# Sheet_this.net
KiCad netlist of a schematic drawn in Altium Designer
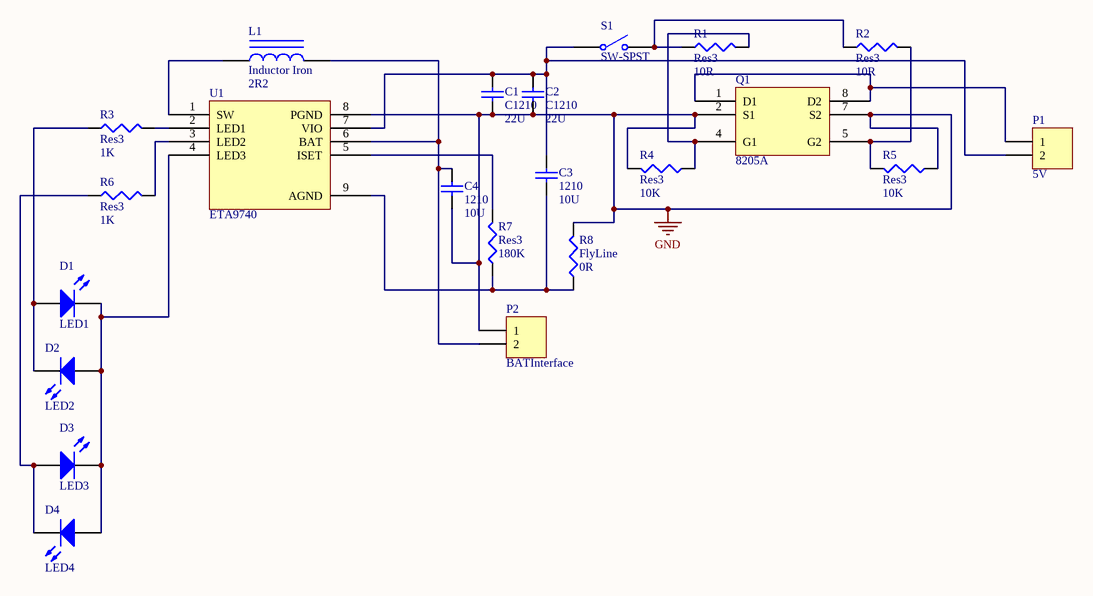
[diagram p0: Sheet.this.SchDoc]

(export (version "E")
  (design (tool "Eeschema 10.0.6"))
  (components
    (comp (ref "C1")
      (value "C1210")
      (footprint "C1210")
      (description "Capacitor")
      (fields (field (name "ALTIUM_VALUE") "22U") (field (name "PUBLISHER") "Altium Limited"))
      (libsource (lib "Miscellaneous Devices") (part "Cap"))
    )
    (comp (ref "C2")
      (value "C1210")
      (footprint "C1210")
      (description "Capacitor")
      (fields (field (name "ALTIUM_VALUE") "22U") (field (name "PUBLISHER") "Altium Limited"))
      (libsource (lib "Miscellaneous Devices") (part "Cap"))
    )
    (comp (ref "C3")
      (value "1210")
      (description "Capacitor")
      (fields (field (name "ALTIUM_VALUE") "10U") (field (name "PUBLISHER") "Altium Limited"))
      (libsource (lib "Miscellaneous Devices") (part "Cap"))
    )
    (comp (ref "C4")
      (value "1210")
      (description "Capacitor")
      (fields (field (name "ALTIUM_VALUE") "10U") (field (name "PUBLISHER") "Altium Limited"))
      (libsource (lib "Miscellaneous Devices") (part "Cap"))
    )
    (comp (ref "D1")
      (value "LED1")
      (footprint "0805D")
      (description "Typical RED, GREEN, YELLOW, AMBER GaAs LED")
      (fields (field (name "PUBLISHER") "Altium Limited"))
      (libsource (lib "Miscellaneous Devices") (part "LED2"))
    )
    (comp (ref "D2")
      (value "LED2")
      (footprint "0805D")
      (description "Typical RED, GREEN, YELLOW, AMBER GaAs LED")
      (fields (field (name "PUBLISHER") "Altium Limited"))
      (libsource (lib "Miscellaneous Devices") (part "LED2"))
    )
    (comp (ref "D3")
      (value "LED3")
      (footprint "0805D")
      (description "Typical RED, GREEN, YELLOW, AMBER GaAs LED")
      (fields (field (name "PUBLISHER") "Altium Limited"))
      (libsource (lib "Miscellaneous Devices") (part "LED2"))
    )
    (comp (ref "D4")
      (value "LED4")
      (footprint "0805D")
      (description "Typical RED, GREEN, YELLOW, AMBER GaAs LED")
      (fields (field (name "PUBLISHER") "Altium Limited"))
      (libsource (lib "Miscellaneous Devices") (part "LED2"))
    )
    (comp (ref "L1")
      (value "Inductor Iron")
      (footprint "L_7x7")
      (description "Magnetic-Core Inductor")
      (fields (field (name "ALTIUM_VALUE") "2R2") (field (name "PUBLISHER") "Altium Limited"))
      (libsource (lib "Miscellaneous Devices") (part "Inductor Iron"))
    )
    (comp (ref "P1")
      (value "5V")
      (footprint "HDR1X2")
      (description "Header, 2-Pin")
      (fields (field (name "PUBLISHER") "Altium Limited"))
      (libsource (lib "Miscellaneous Connectors") (part "Header 2"))
    )
    (comp (ref "P2")
      (value "BATInterface")
      (footprint "HDR1X2")
      (description "Header, 2-Pin, Right Angle")
      (fields (field (name "PUBLISHER") "Altium Limited"))
      (libsource (lib "Miscellaneous Connectors") (part "Header 2H"))
    )
    (comp (ref "Q1") (value "8205A") (footprint "TSSOP8") (libsource (lib "Schlib.this") (part "8205A")))
    (comp (ref "R1")
      (value "Res3")
      (footprint "0805")
      (description "Resistor")
      (fields (field (name "ALTIUM_VALUE") "10R") (field (name "PUBLISHER") "Altium Limited"))
      (libsource (lib "Miscellaneous Devices") (part "Res3"))
    )
    (comp (ref "R2")
      (value "Res3")
      (footprint "0805")
      (description "Resistor")
      (fields (field (name "ALTIUM_VALUE") "10R") (field (name "PUBLISHER") "Altium Limited"))
      (libsource (lib "Miscellaneous Devices") (part "Res3"))
    )
    (comp (ref "R3")
      (value "Res3")
      (footprint "0805")
      (description "Resistor")
      (fields (field (name "ALTIUM_VALUE") "1K") (field (name "PUBLISHER") "Altium Limited"))
      (libsource (lib "Miscellaneous Devices") (part "Res3"))
    )
    (comp (ref "R4")
      (value "Res3")
      (description "Resistor")
      (fields (field (name "ALTIUM_VALUE") "10K") (field (name "PUBLISHER") "Altium Limited"))
      (libsource (lib "Miscellaneous Devices") (part "Res3"))
    )
    (comp (ref "R5")
      (value "Res3")
      (description "Resistor")
      (fields (field (name "ALTIUM_VALUE") "10K") (field (name "PUBLISHER") "Altium Limited"))
      (libsource (lib "Miscellaneous Devices") (part "Res3"))
    )
    (comp (ref "R6")
      (value "Res3")
      (footprint "0805")
      (description "Resistor")
      (fields (field (name "ALTIUM_VALUE") "1K") (field (name "PUBLISHER") "Altium Limited"))
      (libsource (lib "Miscellaneous Devices") (part "Res3"))
    )
    (comp (ref "R7")
      (value "Res3")
      (footprint "0805")
      (description "Resistor")
      (fields (field (name "ALTIUM_VALUE") "180K") (field (name "PUBLISHER") "Altium Limited"))
      (libsource (lib "Miscellaneous Devices") (part "Res3"))
    )
    (comp (ref "R8")
      (value "FlyLine")
      (footprint "PFL1")
      (description "JP")
      (fields (field (name "ALTIUM_VALUE") "0R") (field (name "PUBLISHER") "Altium Limited"))
      (libsource (lib "Miscellaneous Devices") (part "Res3"))
    )
    (comp (ref "S1")
      (value "SW-SPST")
      (footprint "MSS22D18")
      (description "Single-Pole, Single-Throw Switch")
      (fields (field (name "PUBLISHER") "Altium Limited"))
      (libsource (lib "Miscellaneous Devices") (part "SW-SPST"))
    )
    (comp (ref "U1") (value "ETA9740") (footprint "SO-8H") (libsource (lib "Schlib.this") (part "ETA9740")))
  )
  (nets
    (net (code "1") (name "GND") (class "Default")
      (node (ref "C1") (pin "1") (pinfunction "1_1") (pintype "passive"))
      (node (ref "C2") (pin "1") (pinfunction "1_1") (pintype "passive"))
      (node (ref "C4") (pin "1") (pinfunction "1_1") (pintype "passive"))
      (node (ref "P2") (pin "1") (pinfunction "1_1") (pintype "passive"))
      (node (ref "Q1") (pin "2") (pinfunction "S1_2") (pintype "passive"))
      (node (ref "Q1") (pin "7") (pinfunction "S2_7") (pintype "passive"))
      (node (ref "R4") (pin "2") (pinfunction "2_2") (pintype "passive"))
      (node (ref "R5") (pin "1") (pinfunction "1_1") (pintype "passive"))
      (node (ref "R8") (pin "2") (pinfunction "2_2") (pintype "passive"))
      (node (ref "U1") (pin "8") (pinfunction "PGND_8") (pintype "passive"))
    )
    (net (code "2") (name "Net-(D1-A)") (class "Default")
      (node (ref "D1") (pin "1") (pinfunction "A_1") (pintype "passive"))
      (node (ref "D2") (pin "2") (pinfunction "K_2") (pintype "passive"))
      (node (ref "R3") (pin "1") (pinfunction "1_1") (pintype "passive"))
    )
    (net (code "3") (name "Net-(D1-K)") (class "Default")
      (node (ref "D1") (pin "2") (pinfunction "K_2") (pintype "passive"))
      (node (ref "D2") (pin "1") (pinfunction "A_1") (pintype "passive"))
      (node (ref "D3") (pin "2") (pinfunction "K_2") (pintype "passive"))
      (node (ref "D4") (pin "1") (pinfunction "A_1") (pintype "passive"))
      (node (ref "U1") (pin "4") (pinfunction "LED3_4") (pintype "passive"))
    )
    (net (code "4") (name "Net-(D3-A)") (class "Default")
      (node (ref "D3") (pin "1") (pinfunction "A_1") (pintype "passive"))
      (node (ref "D4") (pin "2") (pinfunction "K_2") (pintype "passive"))
      (node (ref "R6") (pin "1") (pinfunction "1_1") (pintype "passive"))
    )
    (net (code "5") (name "Net-(Q1-D1)") (class "Default")
      (node (ref "P1") (pin "1") (pinfunction "1_1") (pintype "passive"))
      (node (ref "Q1") (pin "1") (pinfunction "D1_1") (pintype "passive"))
      (node (ref "Q1") (pin "8") (pinfunction "D2_8") (pintype "passive"))
    )
    (net (code "6") (name "Net-(Q1-G1)") (class "Default")
      (node (ref "Q1") (pin "4") (pinfunction "G1_4") (pintype "passive"))
      (node (ref "R1") (pin "2") (pinfunction "2_2") (pintype "passive"))
      (node (ref "R4") (pin "1") (pinfunction "1_1") (pintype "passive"))
    )
    (net (code "7") (name "Net-(Q1-G2)") (class "Default")
      (node (ref "Q1") (pin "5") (pinfunction "G2_5") (pintype "passive"))
      (node (ref "R2") (pin "2") (pinfunction "2_2") (pintype "passive"))
      (node (ref "R5") (pin "2") (pinfunction "2_2") (pintype "passive"))
    )
    (net (code "8") (name "Net-(S1-COMMON)") (class "Default")
      (node (ref "C1") (pin "2") (pinfunction "2_2") (pintype "passive"))
      (node (ref "C2") (pin "2") (pinfunction "2_2") (pintype "passive"))
      (node (ref "C3") (pin "2") (pinfunction "2_2") (pintype "passive"))
      (node (ref "P1") (pin "2") (pinfunction "2_2") (pintype "passive"))
      (node (ref "S1") (pin "1") (pinfunction "COMMON_1") (pintype "passive"))
      (node (ref "U1") (pin "7") (pinfunction "VIO_7") (pintype "passive"))
    )
    (net (code "9") (name "Net-(S1-NO)") (class "Default")
      (node (ref "R1") (pin "1") (pinfunction "1_1") (pintype "passive"))
      (node (ref "R2") (pin "1") (pinfunction "1_1") (pintype "passive"))
      (node (ref "S1") (pin "2") (pinfunction "NO_2") (pintype "passive"))
    )
    (net (code "10") (name "Net-(U1-AGND)") (class "Default")
      (node (ref "C3") (pin "1") (pinfunction "1_1") (pintype "passive"))
      (node (ref "R7") (pin "1") (pinfunction "1_1") (pintype "passive"))
      (node (ref "R8") (pin "1") (pinfunction "1_1") (pintype "passive"))
      (node (ref "U1") (pin "9") (pinfunction "AGND_9") (pintype "passive"))
    )
    (net (code "11") (name "Net-(U1-BAT)") (class "Default")
      (node (ref "C4") (pin "2") (pinfunction "2_2") (pintype "passive"))
      (node (ref "L1") (pin "2") (pinfunction "2_2") (pintype "passive"))
      (node (ref "P2") (pin "2") (pinfunction "2_2") (pintype "passive"))
      (node (ref "U1") (pin "6") (pinfunction "BAT_6") (pintype "passive"))
    )
    (net (code "12") (name "Net-(U1-ISET)") (class "Default")
      (node (ref "R7") (pin "2") (pinfunction "2_2") (pintype "passive"))
      (node (ref "U1") (pin "5") (pinfunction "ISET_5") (pintype "passive"))
    )
    (net (code "13") (name "Net-(U1-LED1)") (class "Default")
      (node (ref "R3") (pin "2") (pinfunction "2_2") (pintype "passive"))
      (node (ref "U1") (pin "2") (pinfunction "LED1_2") (pintype "passive"))
    )
    (net (code "14") (name "Net-(U1-LED2)") (class "Default")
      (node (ref "R6") (pin "2") (pinfunction "2_2") (pintype "passive"))
      (node (ref "U1") (pin "3") (pinfunction "LED2_3") (pintype "passive"))
    )
    (net (code "15") (name "Net-(U1-SW)") (class "Default")
      (node (ref "L1") (pin "1") (pinfunction "1_1") (pintype "passive"))
      (node (ref "U1") (pin "1") (pinfunction "SW_1") (pintype "passive"))
    )
  )
)
